# MSP430F5529LP_Mini_System.net
KiCad netlist of a schematic drawn in Altium Designer
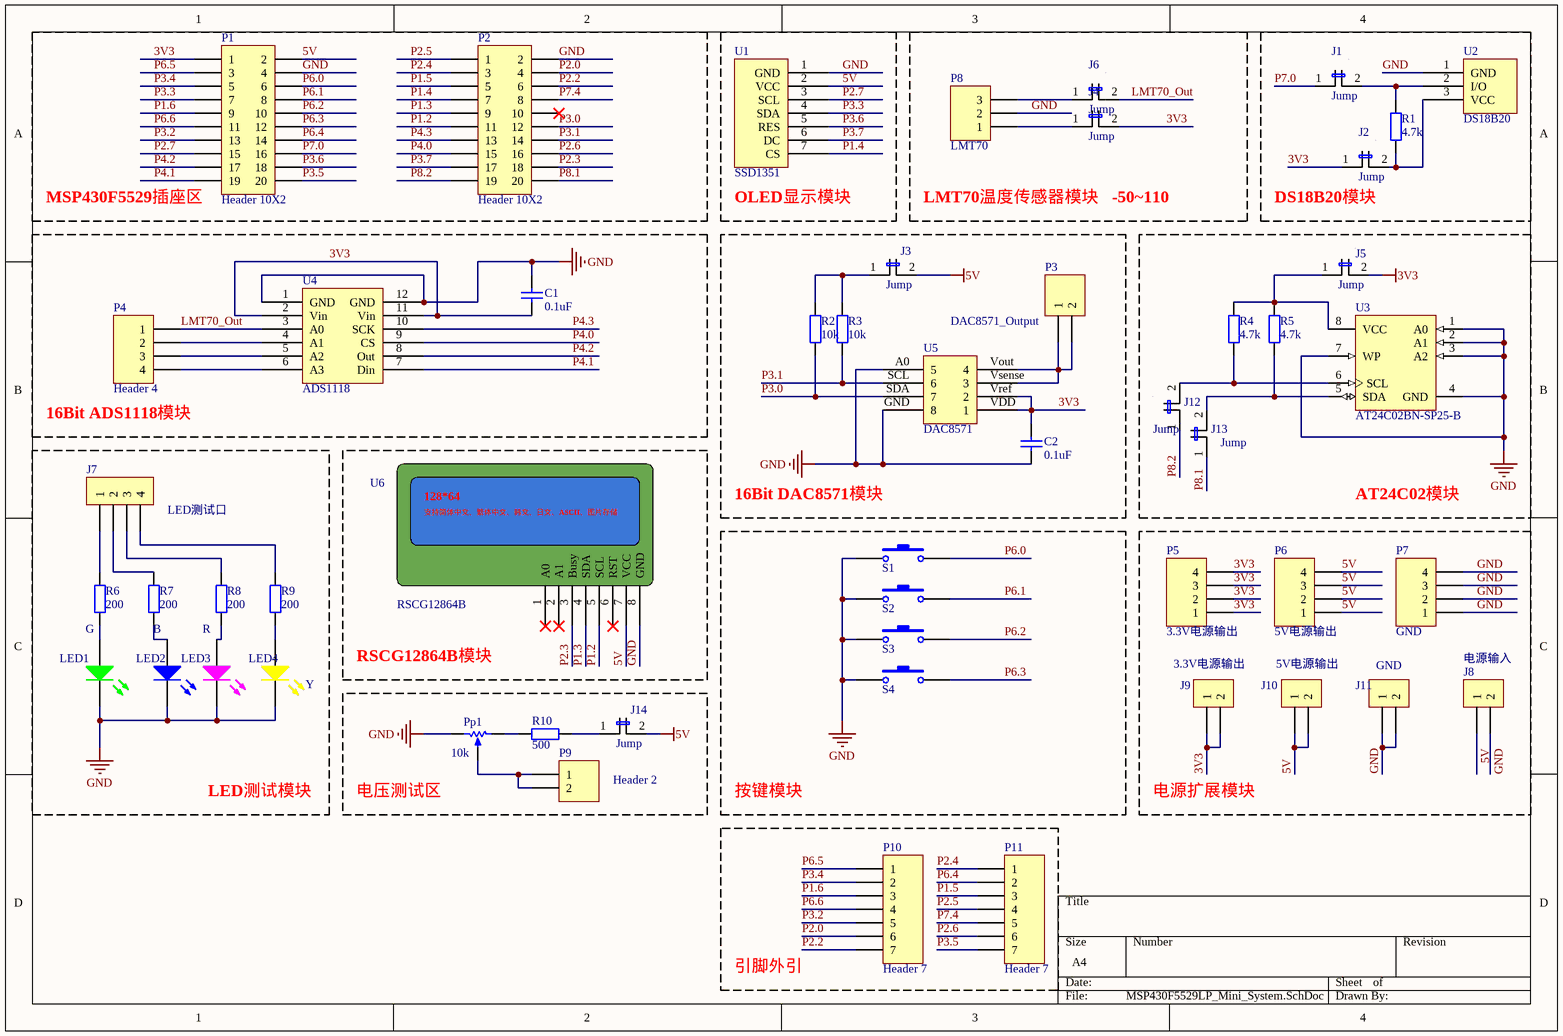
[diagram p0: MSP430F5529LP_Mini_System.SchDoc]

(export (version "E")
  (design (tool "Eeschema 10.0.6"))
  (components
    (comp (ref "C1")
      (value "0.1uF")
      (footprint "Capacitor-Disk-Middle")
      (description "CBB聚乙烯薄膜电容")
      (fields (field (name "VOLTAGE") "63V") (field (name "PUBLISHER") "Altium Limited"))
      (libsource (lib "02-Miscellaneous_Devices_ZSF_Library") (part "Cap Nicklon"))
    )
    (comp (ref "C2")
      (value "0.1uF")
      (footprint "Capacitor-Disk-Middle")
      (description "CBB聚乙烯薄膜电容")
      (fields (field (name "VOLTAGE") "63V") (field (name "PUBLISHER") "Altium Limited"))
      (libsource (lib "02-Miscellaneous_Devices_ZSF_Library") (part "Cap Nicklon"))
    )
    (comp (ref "J1") (value "Jump") (footprint "HDR-1x2") (libsource (lib "Mini_System") (part "Jump")))
    (comp (ref "J2") (value "Jump") (footprint "HDR-1x2") (libsource (lib "Mini_System") (part "Jump")))
    (comp (ref "J3") (value "Jump") (footprint "HDR-1x2") (libsource (lib "Mini_System") (part "Jump")))
    (comp (ref "J4") (value "Jump") (footprint "HDR-1x2") (libsource (lib "Mini_System") (part "Jump")))
    (comp (ref "J5") (value "Jump") (footprint "HDR-1x2") (libsource (lib "Mini_System") (part "Jump")))
    (comp (ref "J6") (value "Jump") (footprint "HDR-1x2") (libsource (lib "Mini_System") (part "Jump")))
    (comp (ref "J7")
      (value "LED测试口")
      (footprint "HDR-1X4_M")
      (description "排针")
      (libsource (lib "Connector") (part "HDR1X4"))
    )
    (comp (ref "J8")
      (value "电源输入")
      (footprint "Connector:XH2.54-2P")
      (description "连接器")
      (libsource (lib "Connector") (part "CON2"))
    )
    (comp (ref "J9")
      (value "3.3V电源输出")
      (footprint "Connector:WJ500V-5.08-2")
      (description "接线端子")
      (libsource (lib "Connector") (part "KF128-5.08MM-2P"))
    )
    (comp (ref "J10")
      (value "5V电源输出")
      (footprint "Connector:WJ500V-5.08-2")
      (description "接线端子")
      (libsource (lib "Connector") (part "KF128-5.08MM-2P"))
    )
    (comp (ref "J11")
      (value "GND")
      (footprint "Connector:WJ500V-5.08-2")
      (description "接线端子")
      (libsource (lib "Connector") (part "KF128-5.08MM-2P"))
    )
    (comp (ref "J12") (value "Jump") (footprint "HDR-1x2") (libsource (lib "Mini_System") (part "Jump")))
    (comp (ref "J13") (value "Jump") (footprint "HDR-1x2") (libsource (lib "Mini_System") (part "Jump")))
    (comp (ref "J14") (value "Jump") (footprint "HDR-1x2") (libsource (lib "Mini_System") (part "Jump")))
    (comp (ref "LED1")
      (value "G")
      (footprint "LED-R3-H5-SINGLE-G")
      (description "Typical INFRARED GaAs LED")
      (fields (field (name "PUBLISHER") "Altium Limited"))
      (libsource (lib "03-EButterflyIntegratedLibrary") (part "LED-3-G"))
    )
    (comp (ref "LED2")
      (value "B")
      (footprint "LED-R3-H5-SINGLE-B")
      (description "Typical INFRARED GaAs LED")
      (fields (field (name "PUBLISHER") "Altium Limited"))
      (libsource (lib "03-EButterflyIntegratedLibrary") (part "LED-3-B"))
    )
    (comp (ref "LED3")
      (value "R")
      (footprint "LED-R3-H5-SINGLE-R")
      (description "Typical INFRARED GaAs LED")
      (fields (field (name "PUBLISHER") "Altium Limited"))
      (libsource (lib "03-EButterflyIntegratedLibrary") (part "LED-3-R"))
    )
    (comp (ref "LED4")
      (value "Y")
      (footprint "LED-R3-H5-SINGLE-Y")
      (description "Typical INFRARED GaAs LED")
      (fields (field (name "PUBLISHER") "Altium Limited"))
      (libsource (lib "03-EButterflyIntegratedLibrary") (part "LED-3-Y"))
    )
    (comp (ref "P1")
      (value "Header 10X2")
      (footprint "HDR2X10")
      (description "Header, 10-Pin, Dual row")
      (fields (field (name "PUBLISHER") "Altium Limited"))
      (libsource (lib "03-EButterflyIntegratedLibrary") (part "Header 10X2"))
    )
    (comp (ref "P2")
      (value "Header 10X2")
      (footprint "HDR2X10")
      (description "Header, 10-Pin, Dual row")
      (fields (field (name "PUBLISHER") "Altium Limited"))
      (libsource (lib "03-EButterflyIntegratedLibrary") (part "Header 10X2"))
    )
    (comp (ref "P3")
      (value "DAC8571_Output")
      (footprint "HDR-1X2_H")
      (description "Header, 2-Pin")
      (fields (field (name "PUBLISHER") "Altium Limited"))
      (libsource (lib "03-EButterflyIntegratedLibrary") (part "Header 2"))
    )
    (comp (ref "P4")
      (value "Header 4")
      (footprint "HDR1X4")
      (description "Header, 4-Pin")
      (fields (field (name "PUBLISHER") "Altium Limited"))
      (libsource (lib "03-EButterflyIntegratedLibrary") (part "Header 4"))
    )
    (comp (ref "P5")
      (value "3.3V电源输出")
      (footprint "HDR1X4")
      (description "Header, 4-Pin")
      (fields (field (name "PUBLISHER") "Altium Limited"))
      (libsource (lib "") (part "Header 4_1"))
    )
    (comp (ref "P6")
      (value "5V电源输出")
      (footprint "HDR1X4")
      (description "Header, 4-Pin")
      (fields (field (name "PUBLISHER") "Altium Limited"))
      (libsource (lib "") (part "Header 4_1"))
    )
    (comp (ref "P7")
      (value "GND")
      (footprint "HDR1X4")
      (description "Header, 4-Pin")
      (fields (field (name "PUBLISHER") "Altium Limited"))
      (libsource (lib "") (part "Header 4_1"))
    )
    (comp (ref "P8")
      (value "LMT70")
      (footprint "HDR-1X3_M")
      (description "Header, 3-Pin")
      (fields (field (name "PUBLISHER") "Altium Limited"))
      (libsource (lib "03-EButterflyIntegratedLibrary") (part "Header 3"))
    )
    (comp (ref "P9")
      (value "Header 2")
      (footprint "HDR1X2")
      (description "Header, 2-Pin")
      (fields (field (name "PUBLISHER") "Altium Limited"))
      (libsource (lib "") (part "Header 2_1"))
    )
    (comp (ref "P10")
      (value "Header 7")
      (footprint "HDR-1X7_M")
      (description "Header, 7-Pin")
      (fields (field (name "PUBLISHER") "Altium Limited"))
      (libsource (lib "Miscellaneous Connectors") (part "Header 7"))
    )
    (comp (ref "P11")
      (value "Header 7")
      (footprint "HDR-1X7_M")
      (description "Header, 7-Pin")
      (fields (field (name "PUBLISHER") "Altium Limited"))
      (libsource (lib "Miscellaneous Connectors") (part "Header 7"))
    )
    (comp (ref "Pp1")
      (value "10k")
      (footprint "RP_3296")
      (description "3296电位器")
      (libsource (lib "02-Miscellaneous_Devices_ZSF_Library") (part "RP_3296"))
    )
    (comp (ref "R1")
      (value "4.7k")
      (footprint "Resistors:RS 1/4W")
      (description "Resistor")
      (fields (field (name "PUBLISHER") "Altium Limited"))
      (libsource (lib "Miscellaneous Devices") (part "Res2"))
    )
    (comp (ref "R2")
      (value "10k")
      (footprint "Resistors:RS 1/4W")
      (description "Resistor")
      (fields (field (name "PUBLISHER") "Altium Limited"))
      (libsource (lib "Miscellaneous Devices") (part "Res2"))
    )
    (comp (ref "R3")
      (value "10k")
      (footprint "Resistors:RS 1/4W")
      (description "Resistor")
      (fields (field (name "PUBLISHER") "Altium Limited"))
      (libsource (lib "Miscellaneous Devices") (part "Res2"))
    )
    (comp (ref "R4")
      (value "4.7k")
      (footprint "Resistors:RS 1/4W")
      (description "Resistor")
      (fields (field (name "PUBLISHER") "Altium Limited"))
      (libsource (lib "Miscellaneous Devices") (part "Res2"))
    )
    (comp (ref "R5")
      (value "4.7k")
      (footprint "Resistors:RS 1/4W")
      (description "Resistor")
      (fields (field (name "PUBLISHER") "Altium Limited"))
      (libsource (lib "Miscellaneous Devices") (part "Res2"))
    )
    (comp (ref "R6")
      (value "200")
      (footprint "Resistors:RS 1/4W")
      (description "Resistor")
      (fields (field (name "PUBLISHER") "Altium Limited"))
      (libsource (lib "Miscellaneous Devices") (part "Res2"))
    )
    (comp (ref "R7")
      (value "200")
      (footprint "Resistors:RS 1/4W")
      (description "Resistor")
      (fields (field (name "PUBLISHER") "Altium Limited"))
      (libsource (lib "Miscellaneous Devices") (part "Res2"))
    )
    (comp (ref "R8")
      (value "200")
      (footprint "Resistors:RS 1/4W")
      (description "Resistor")
      (fields (field (name "PUBLISHER") "Altium Limited"))
      (libsource (lib "Miscellaneous Devices") (part "Res2"))
    )
    (comp (ref "R9")
      (value "200")
      (footprint "Resistors:RS 1/4W")
      (description "Resistor")
      (fields (field (name "PUBLISHER") "Altium Limited"))
      (libsource (lib "Miscellaneous Devices") (part "Res2"))
    )
    (comp (ref "R10")
      (value "500")
      (footprint "Resistors:RS 1/4W")
      (description "Resistor")
      (fields (field (name "PUBLISHER") "Altium Limited"))
      (libsource (lib "") (part "Res2_1"))
    )
    (comp (ref "S1")
      (value "S1")
      (footprint "BUTTON_6*6")
      (description "Tactile Switch触觉开关")
      (fields (field (name "PUBLISHER") "Altium Limited"))
      (libsource (lib "02-Miscellaneous_Devices_ZSF_Library") (part "SW-PB"))
    )
    (comp (ref "S2")
      (value "S2")
      (footprint "BUTTON_6*6")
      (description "Tactile Switch触觉开关")
      (fields (field (name "PUBLISHER") "Altium Limited"))
      (libsource (lib "02-Miscellaneous_Devices_ZSF_Library") (part "SW-PB"))
    )
    (comp (ref "S3")
      (value "S3")
      (footprint "BUTTON_6*6")
      (description "Tactile Switch触觉开关")
      (fields (field (name "PUBLISHER") "Altium Limited"))
      (libsource (lib "02-Miscellaneous_Devices_ZSF_Library") (part "SW-PB"))
    )
    (comp (ref "S4")
      (value "S4")
      (footprint "BUTTON_6*6")
      (description "Tactile Switch触觉开关")
      (fields (field (name "PUBLISHER") "Altium Limited"))
      (libsource (lib "02-Miscellaneous_Devices_ZSF_Library") (part "SW-PB"))
    )
    (comp (ref "U1")
      (value "SSD1351")
      (footprint "HDR-1X7_M")
      (description "1.5寸彩色OLED")
      (libsource (lib "Mini_System") (part "1.5'OLED RGB SSD1351"))
    )
    (comp (ref "U2")
      (value "DS18B20")
      (footprint "HDR-1X3_Y")
      (libsource (lib "02-Miscellaneous_Devices_ZSF_Library") (part "DS18B20"))
    )
    (comp (ref "U3")
      (value "AT24C02BN-SP25-B")
      (footprint "DIP8-300_MH")
      (fields (field (name "PUBLISHER") "Altium Limited"))
      (libsource (lib "altium-import") (part "root_0_mirrored_AT24C02BN-SP25-B_"))
    )
    (comp (ref "U4")
      (value "ADS1118")
      (footprint "dip12")
      (description "16位ADC芯片，将模拟电压信号转化为数字信号供单片机处理")
      (libsource (lib "Mini_System") (part "ADS1118"))
    )
    (comp (ref "U5")
      (value "DAC8571")
      (footprint "DIP8-300_MH")
      (description "16位DAC芯片，将数字量转化为模拟电压输出")
      (libsource (lib "Mini_System") (part "DAC8571"))
    )
    (comp (ref "U6")
      (value "RSCG12864B")
      (footprint "HDR-1X8_M")
      (libsource (lib "Mini_System") (part "RSCG12864B"))
    )
  )
  (nets
    (net (code "1") (name "/LMT70_Out") (class "Default")
      (node (ref "J6") (pin "2") (pinfunction "2_2") (pintype "passive"))
      (node (ref "P4") (pin "1") (pinfunction "1_1") (pintype "passive"))
      (node (ref "U4") (pin "3") (pinfunction "A0_3") (pintype "passive"))
    )
    (net (code "2") (name "/P1.2") (class "Default")
      (node (ref "P2") (pin "11") (pinfunction "11_11") (pintype "passive"))
      (node (ref "U6") (pin "5") (pinfunction "SCL_5") (pintype "passive"))
    )
    (net (code "3") (name "/P1.3") (class "Default")
      (node (ref "P2") (pin "9") (pinfunction "9_9") (pintype "passive"))
      (node (ref "U6") (pin "4") (pinfunction "SDA_4") (pintype "passive"))
    )
    (net (code "4") (name "/P1.4") (class "Default")
      (node (ref "P2") (pin "7") (pinfunction "7_7") (pintype "passive"))
      (node (ref "U1") (pin "7") (pinfunction "CS_7") (pintype "passive"))
    )
    (net (code "5") (name "/P1.5") (class "Default")
      (node (ref "P11") (pin "3") (pinfunction "3_3") (pintype "passive"))
      (node (ref "P2") (pin "5") (pinfunction "5_5") (pintype "passive"))
    )
    (net (code "6") (name "/P1.6") (class "Default")
      (node (ref "P1") (pin "9") (pinfunction "9_9") (pintype "passive"))
      (node (ref "P10") (pin "3") (pinfunction "3_3") (pintype "passive"))
    )
    (net (code "7") (name "/P2.0") (class "Default")
      (node (ref "P10") (pin "6") (pinfunction "6_6") (pintype "passive"))
      (node (ref "P2") (pin "4") (pinfunction "4_4") (pintype "passive"))
    )
    (net (code "8") (name "/P2.2") (class "Default")
      (node (ref "P10") (pin "7") (pinfunction "7_7") (pintype "passive"))
      (node (ref "P2") (pin "6") (pinfunction "6_6") (pintype "passive"))
    )
    (net (code "9") (name "/P2.3") (class "Default")
      (node (ref "P2") (pin "18") (pinfunction "18_18") (pintype "passive"))
      (node (ref "U6") (pin "3") (pinfunction "Busy_3") (pintype "passive"))
    )
    (net (code "10") (name "/P2.4") (class "Default")
      (node (ref "P11") (pin "1") (pinfunction "1_1") (pintype "passive"))
      (node (ref "P2") (pin "3") (pinfunction "3_3") (pintype "passive"))
    )
    (net (code "11") (name "/P2.5") (class "Default")
      (node (ref "P11") (pin "4") (pinfunction "4_4") (pintype "passive"))
      (node (ref "P2") (pin "1") (pinfunction "1_1") (pintype "passive"))
    )
    (net (code "12") (name "/P2.6") (class "Default")
      (node (ref "P11") (pin "6") (pinfunction "6_6") (pintype "passive"))
      (node (ref "P2") (pin "16") (pinfunction "16_16") (pintype "passive"))
    )
    (net (code "13") (name "/P2.7") (class "Default")
      (node (ref "P1") (pin "15") (pinfunction "15_15") (pintype "passive"))
      (node (ref "U1") (pin "3") (pinfunction "SCL_3") (pintype "passive"))
    )
    (net (code "14") (name "/P3.0") (class "Default")
      (node (ref "P2") (pin "12") (pinfunction "12_12") (pintype "passive"))
      (node (ref "R2") (pin "1") (pinfunction "1_1") (pintype "passive"))
      (node (ref "U5") (pin "SDA") (pinfunction "7_SDA") (pintype "passive"))
    )
    (net (code "15") (name "/P3.1") (class "Default")
      (node (ref "P2") (pin "14") (pinfunction "14_14") (pintype "passive"))
      (node (ref "R3") (pin "1") (pinfunction "1_1") (pintype "passive"))
      (node (ref "U5") (pin "SCL") (pinfunction "6_SCL") (pintype "passive"))
    )
    (net (code "16") (name "/P3.2") (class "Default")
      (node (ref "P1") (pin "13") (pinfunction "13_13") (pintype "passive"))
      (node (ref "P10") (pin "5") (pinfunction "5_5") (pintype "passive"))
    )
    (net (code "17") (name "/P3.3") (class "Default")
      (node (ref "P1") (pin "7") (pinfunction "7_7") (pintype "passive"))
      (node (ref "U1") (pin "4") (pinfunction "SDA_4") (pintype "passive"))
    )
    (net (code "18") (name "/P3.4") (class "Default")
      (node (ref "P1") (pin "5") (pinfunction "5_5") (pintype "passive"))
      (node (ref "P10") (pin "2") (pinfunction "2_2") (pintype "passive"))
    )
    (net (code "19") (name "/P3.5") (class "Default")
      (node (ref "P1") (pin "20") (pinfunction "20_20") (pintype "passive"))
      (node (ref "P11") (pin "7") (pinfunction "7_7") (pintype "passive"))
    )
    (net (code "20") (name "/P3.6") (class "Default")
      (node (ref "P1") (pin "18") (pinfunction "18_18") (pintype "passive"))
      (node (ref "U1") (pin "5") (pinfunction "RES_5") (pintype "passive"))
    )
    (net (code "21") (name "/P3.7") (class "Default")
      (node (ref "P2") (pin "17") (pinfunction "17_17") (pintype "passive"))
      (node (ref "U1") (pin "6") (pinfunction "DC_6") (pintype "passive"))
    )
    (net (code "22") (name "/P4.0") (class "Default")
      (node (ref "P2") (pin "15") (pinfunction "15_15") (pintype "passive"))
      (node (ref "U4") (pin "9") (pinfunction "CS_9") (pintype "passive"))
    )
    (net (code "23") (name "/P4.1") (class "Default")
      (node (ref "P1") (pin "19") (pinfunction "19_19") (pintype "passive"))
      (node (ref "U4") (pin "7") (pinfunction "Din_7") (pintype "passive"))
    )
    (net (code "24") (name "/P4.2") (class "Default")
      (node (ref "P1") (pin "17") (pinfunction "17_17") (pintype "passive"))
      (node (ref "U4") (pin "8") (pinfunction "Out_8") (pintype "passive"))
    )
    (net (code "25") (name "/P4.3") (class "Default")
      (node (ref "P2") (pin "13") (pinfunction "13_13") (pintype "passive"))
      (node (ref "U4") (pin "10") (pinfunction "SCK_10") (pintype "passive"))
    )
    (net (code "26") (name "/P6.0") (class "Default")
      (node (ref "P1") (pin "6") (pinfunction "6_6") (pintype "passive"))
      (node (ref "S1") (pin "2") (pinfunction "2_2") (pintype "passive"))
    )
    (net (code "27") (name "/P6.1") (class "Default")
      (node (ref "P1") (pin "8") (pinfunction "8_8") (pintype "passive"))
      (node (ref "S2") (pin "2") (pinfunction "2_2") (pintype "passive"))
    )
    (net (code "28") (name "/P6.2") (class "Default")
      (node (ref "P1") (pin "10") (pinfunction "10_10") (pintype "passive"))
      (node (ref "S3") (pin "2") (pinfunction "2_2") (pintype "passive"))
    )
    (net (code "29") (name "/P6.3") (class "Default")
      (node (ref "P1") (pin "12") (pinfunction "12_12") (pintype "passive"))
      (node (ref "S4") (pin "2") (pinfunction "2_2") (pintype "passive"))
    )
    (net (code "30") (name "/P6.4") (class "Default")
      (node (ref "P1") (pin "14") (pinfunction "14_14") (pintype "passive"))
      (node (ref "P11") (pin "2") (pinfunction "2_2") (pintype "passive"))
    )
    (net (code "31") (name "/P6.5") (class "Default")
      (node (ref "P1") (pin "3") (pinfunction "3_3") (pintype "passive"))
      (node (ref "P10") (pin "1") (pinfunction "1_1") (pintype "passive"))
    )
    (net (code "32") (name "/P6.6") (class "Default")
      (node (ref "P1") (pin "11") (pinfunction "11_11") (pintype "passive"))
      (node (ref "P10") (pin "4") (pinfunction "4_4") (pintype "passive"))
    )
    (net (code "33") (name "/P7.0") (class "Default")
      (node (ref "J1") (pin "1") (pinfunction "1_1") (pintype "passive"))
      (node (ref "P1") (pin "16") (pinfunction "16_16") (pintype "passive"))
    )
    (net (code "34") (name "/P7.4") (class "Default")
      (node (ref "P11") (pin "5") (pinfunction "5_5") (pintype "passive"))
      (node (ref "P2") (pin "8") (pinfunction "8_8") (pintype "passive"))
    )
    (net (code "35") (name "/P8.1") (class "Default")
      (node (ref "J13") (pin "1") (pinfunction "1_1") (pintype "passive"))
      (node (ref "P2") (pin "20") (pinfunction "20_20") (pintype "passive"))
    )
    (net (code "36") (name "/P8.2") (class "Default")
      (node (ref "J12") (pin "1") (pinfunction "1_1") (pintype "passive"))
      (node (ref "P2") (pin "19") (pinfunction "19_19") (pintype "passive"))
    )
    (net (code "37") (name "3V3") (class "Default")
      (node (ref "C1") (pin "1") (pinfunction "1_1") (pintype "passive"))
      (node (ref "C2") (pin "2") (pinfunction "2_2") (pintype "passive"))
      (node (ref "J2") (pin "1") (pinfunction "1_1") (pintype "passive"))
      (node (ref "J4") (pin "2") (pinfunction "2_2") (pintype "passive"))
      (node (ref "J5") (pin "2") (pinfunction "2_2") (pintype "passive"))
      (node (ref "J9") (pin "1") (pinfunction "1_1") (pintype "passive"))
      (node (ref "J9") (pin "2") (pinfunction "2_2") (pintype "passive"))
      (node (ref "P1") (pin "1") (pinfunction "1_1") (pintype "passive"))
      (node (ref "P5") (pin "1") (pinfunction "1_1") (pintype "passive"))
      (node (ref "P5") (pin "2") (pinfunction "2_2") (pintype "passive"))
      (node (ref "P5") (pin "3") (pinfunction "3_3") (pintype "passive"))
      (node (ref "P5") (pin "4") (pinfunction "4_4") (pintype "passive"))
      (node (ref "U4") (pin "11") (pinfunction "Vin_11") (pintype "passive"))
      (node (ref "U4") (pin "2") (pinfunction "Vin_2") (pintype "passive"))
      (node (ref "U5") (pin "VDD") (pinfunction "1_VDD") (pintype "passive"))
      (node (ref "U5") (pin "Vref") (pinfunction "2_Vref") (pintype "passive"))
    )
    (net (code "38") (name "5V") (class "Default")
      (node (ref "J10") (pin "1") (pinfunction "1_1") (pintype "passive"))
      (node (ref "J10") (pin "2") (pinfunction "2_2") (pintype "passive"))
      (node (ref "J14") (pin "2") (pinfunction "2_2") (pintype "passive"))
      (node (ref "J3") (pin "2") (pinfunction "2_2") (pintype "passive"))
      (node (ref "J8") (pin "1") (pinfunction "1_1") (pintype "passive"))
      (node (ref "P1") (pin "2") (pinfunction "2_2") (pintype "passive"))
      (node (ref "P6") (pin "1") (pinfunction "1_1") (pintype "passive"))
      (node (ref "P6") (pin "2") (pinfunction "2_2") (pintype "passive"))
      (node (ref "P6") (pin "3") (pinfunction "3_3") (pintype "passive"))
      (node (ref "P6") (pin "4") (pinfunction "4_4") (pintype "passive"))
      (node (ref "U1") (pin "2") (pinfunction "VCC_2") (pintype "passive"))
      (node (ref "U6") (pin "7") (pinfunction "VCC_7") (pintype "passive"))
    )
    (net (code "39") (name "GND") (class "Default")
      (node (ref "C1") (pin "2") (pinfunction "2_2") (pintype "passive"))
      (node (ref "C2") (pin "1") (pinfunction "1_1") (pintype "passive"))
      (node (ref "J11") (pin "1") (pinfunction "1_1") (pintype "passive"))
      (node (ref "J11") (pin "2") (pinfunction "2_2") (pintype "passive"))
      (node (ref "J8") (pin "2") (pinfunction "2_2") (pintype "passive"))
      (node (ref "LED1") (pin "2") (pinfunction "K_2") (pintype "passive"))
      (node (ref "LED2") (pin "2") (pinfunction "K_2") (pintype "passive"))
      (node (ref "LED3") (pin "2") (pinfunction "K_2") (pintype "passive"))
      (node (ref "LED4") (pin "2") (pinfunction "K_2") (pintype "passive"))
      (node (ref "P1") (pin "4") (pinfunction "4_4") (pintype "passive"))
      (node (ref "P2") (pin "2") (pinfunction "2_2") (pintype "passive"))
      (node (ref "P7") (pin "1") (pinfunction "1_1") (pintype "passive"))
      (node (ref "P7") (pin "2") (pinfunction "2_2") (pintype "passive"))
      (node (ref "P7") (pin "3") (pinfunction "3_3") (pintype "passive"))
      (node (ref "P7") (pin "4") (pinfunction "4_4") (pintype "passive"))
      (node (ref "P8") (pin "2") (pinfunction "2_2") (pintype "passive"))
      (node (ref "Pp1") (pin "3") (pinfunction "BOT_3") (pintype "passive"))
      (node (ref "S1") (pin "1") (pinfunction "1_1") (pintype "passive"))
      (node (ref "S2") (pin "1") (pinfunction "1_1") (pintype "passive"))
      (node (ref "S3") (pin "1") (pinfunction "1_1") (pintype "passive"))
      (node (ref "S4") (pin "1") (pinfunction "1_1") (pintype "passive"))
      (node (ref "U1") (pin "1") (pinfunction "GND_1") (pintype "passive"))
      (node (ref "U2") (pin "1") (pinfunction "GND_1") (pintype "passive"))
      (node (ref "U3") (pin "1") (pinfunction "A0_1") (pintype "input"))
      (node (ref "U3") (pin "2") (pinfunction "A1_2") (pintype "input"))
      (node (ref "U3") (pin "3") (pinfunction "A2_3") (pintype "input"))
      (node (ref "U3") (pin "4") (pinfunction "GND_4") (pintype "power_in"))
      (node (ref "U3") (pin "7") (pinfunction "WP_7") (pintype "input"))
      (node (ref "U4") (pin "1") (pinfunction "GND_1") (pintype "passive"))
      (node (ref "U4") (pin "12") (pinfunction "GND_12") (pintype "passive"))
      (node (ref "U5") (pin "A0") (pinfunction "5_A0") (pintype "passive"))
      (node (ref "U5") (pin "GND") (pinfunction "8_GND") (pintype "passive"))
      (node (ref "U6") (pin "8") (pinfunction "GND_8") (pintype "passive"))
    )
    (net (code "40") (name "Net-(J3-Pad1)") (class "Default")
      (node (ref "J3") (pin "1") (pinfunction "1_1") (pintype "passive"))
      (node (ref "R2") (pin "2") (pinfunction "2_2") (pintype "passive"))
      (node (ref "R3") (pin "2") (pinfunction "2_2") (pintype "passive"))
    )
    (net (code "41") (name "Net-(J4-Pad1)") (class "Default")
      (node (ref "J4") (pin "1") (pinfunction "1_1") (pintype "passive"))
      (node (ref "P8") (pin "1") (pinfunction "1_1") (pintype "passive"))
    )
    (net (code "42") (name "Net-(J6-Pad1)") (class "Default")
      (node (ref "J6") (pin "1") (pinfunction "1_1") (pintype "passive"))
      (node (ref "P8") (pin "3") (pinfunction "3_3") (pintype "passive"))
    )
    (net (code "43") (name "Net-(J7-Pad1)") (class "Default")
      (node (ref "J7") (pin "1") (pinfunction "1_1") (pintype "passive"))
      (node (ref "R6") (pin "2") (pinfunction "2_2") (pintype "passive"))
    )
    (net (code "44") (name "Net-(J7-Pad2)") (class "Default")
      (node (ref "J7") (pin "2") (pinfunction "2_2") (pintype "passive"))
      (node (ref "R7") (pin "2") (pinfunction "2_2") (pintype "passive"))
    )
    (net (code "45") (name "Net-(J7-Pad3)") (class "Default")
      (node (ref "J7") (pin "3") (pinfunction "3_3") (pintype "passive"))
      (node (ref "R8") (pin "2") (pinfunction "2_2") (pintype "passive"))
    )
    (net (code "46") (name "Net-(J7-Pad4)") (class "Default")
      (node (ref "J7") (pin "4") (pinfunction "4_4") (pintype "passive"))
      (node (ref "R9") (pin "2") (pinfunction "2_2") (pintype "passive"))
    )
    (net (code "47") (name "Net-(J14-Pad1)") (class "Default")
      (node (ref "J14") (pin "1") (pinfunction "1_1") (pintype "passive"))
      (node (ref "R10") (pin "1") (pinfunction "1_1") (pintype "passive"))
    )
    (net (code "48") (name "Net-(LED1-A)") (class "Default")
      (node (ref "LED1") (pin "1") (pinfunction "A_1") (pintype "passive"))
      (node (ref "R6") (pin "1") (pinfunction "1_1") (pintype "passive"))
    )
    (net (code "49") (name "Net-(LED2-A)") (class "Default")
      (node (ref "LED2") (pin "1") (pinfunction "A_1") (pintype "passive"))
      (node (ref "R7") (pin "1") (pinfunction "1_1") (pintype "passive"))
    )
    (net (code "50") (name "Net-(LED3-A)") (class "Default")
      (node (ref "LED3") (pin "1") (pinfunction "A_1") (pintype "passive"))
      (node (ref "R8") (pin "1") (pinfunction "1_1") (pintype "passive"))
    )
    (net (code "51") (name "Net-(LED4-A)") (class "Default")
      (node (ref "LED4") (pin "1") (pinfunction "A_1") (pintype "passive"))
      (node (ref "R9") (pin "1") (pinfunction "1_1") (pintype "passive"))
    )
    (net (code "52") (name "Net-(Pp1-TAP)") (class "Default")
      (node (ref "P9") (pin "1") (pinfunction "1_1") (pintype "passive"))
      (node (ref "P9") (pin "2") (pinfunction "2_2") (pintype "passive"))
      (node (ref "Pp1") (pin "2") (pinfunction "TAP_2") (pintype "passive"))
    )
    (net (code "53") (name "Net-(Pp1-TOP)") (class "Default")
      (node (ref "Pp1") (pin "1") (pinfunction "TOP_1") (pintype "passive"))
      (node (ref "R10") (pin "2") (pinfunction "2_2") (pintype "passive"))
    )
    (net (code "54") (name "Net-(U2-I{slash}O)") (class "Default")
      (node (ref "J1") (pin "2") (pinfunction "2_2") (pintype "passive"))
      (node (ref "R1") (pin "2") (pinfunction "2_2") (pintype "passive"))
      (node (ref "U2") (pin "2") (pinfunction "I/O_2") (pintype "passive"))
    )
    (net (code "55") (name "Net-(U2-VCC)") (class "Default")
      (node (ref "J2") (pin "2") (pinfunction "2_2") (pintype "passive"))
      (node (ref "R1") (pin "1") (pinfunction "1_1") (pintype "passive"))
      (node (ref "U2") (pin "3") (pinfunction "VCC_3") (pintype "passive"))
    )
    (net (code "56") (name "Net-(U3-SCL)") (class "Default")
      (node (ref "J12") (pin "2") (pinfunction "2_2") (pintype "passive"))
      (node (ref "R4") (pin "1") (pinfunction "1_1") (pintype "passive"))
      (node (ref "U3") (pin "6") (pinfunction "SCL_6") (pintype "input"))
    )
    (net (code "57") (name "Net-(U3-SDA)") (class "Default")
      (node (ref "J13") (pin "2") (pinfunction "2_2") (pintype "passive"))
      (node (ref "R5") (pin "1") (pinfunction "1_1") (pintype "passive"))
      (node (ref "U3") (pin "5") (pinfunction "SDA_5") (pintype "bidirectional"))
    )
    (net (code "58") (name "Net-(U3-VCC)") (class "Default")
      (node (ref "J5") (pin "1") (pinfunction "1_1") (pintype "passive"))
      (node (ref "R4") (pin "2") (pinfunction "2_2") (pintype "passive"))
      (node (ref "R5") (pin "2") (pinfunction "2_2") (pintype "passive"))
      (node (ref "U3") (pin "8") (pinfunction "VCC_8") (pintype "power_in"))
    )
    (net (code "59") (name "Net-(U4-A1)") (class "Default")
      (node (ref "P4") (pin "2") (pinfunction "2_2") (pintype "passive"))
      (node (ref "U4") (pin "4") (pinfunction "A1_4") (pintype "passive"))
    )
    (net (code "60") (name "Net-(U4-A2)") (class "Default")
      (node (ref "P4") (pin "3") (pinfunction "3_3") (pintype "passive"))
      (node (ref "U4") (pin "5") (pinfunction "A2_5") (pintype "passive"))
    )
    (net (code "61") (name "Net-(U4-A3)") (class "Default")
      (node (ref "P4") (pin "4") (pinfunction "4_4") (pintype "passive"))
      (node (ref "U4") (pin "6") (pinfunction "A3_6") (pintype "passive"))
    )
    (net (code "62") (name "Net-(U5-3)") (class "Default")
      (node (ref "P3") (pin "1") (pinfunction "1_1") (pintype "passive"))
      (node (ref "P3") (pin "2") (pinfunction "2_2") (pintype "passive"))
      (node (ref "U5") (pin "Vout") (pinfunction "4_Vout") (pintype "passive"))
      (node (ref "U5") (pin "Vsense") (pinfunction "3_Vsense") (pintype "passive"))
    )
    (net (code "63") (name "unconnected-(P2-Pad10)") (class "Default")
      (node (ref "P2") (pin "10") (pinfunction "10_10") (pintype "passive+no_connect"))
    )
    (net (code "64") (name "unconnected-(U6-A0-Pad1)") (class "Default")
      (node (ref "U6") (pin "1") (pinfunction "A0_1") (pintype "passive+no_connect"))
    )
    (net (code "65") (name "unconnected-(U6-A1-Pad2)") (class "Default")
      (node (ref "U6") (pin "2") (pinfunction "A1_2") (pintype "passive+no_connect"))
    )
    (net (code "66") (name "unconnected-(U6-RST-Pad6)") (class "Default")
      (node (ref "U6") (pin "6") (pinfunction "RST_6") (pintype "passive+no_connect"))
    )
  )
)
